# H-bridge_and_gate_drivers.net
KiCad netlist of a schematic drawn in Altium Designer
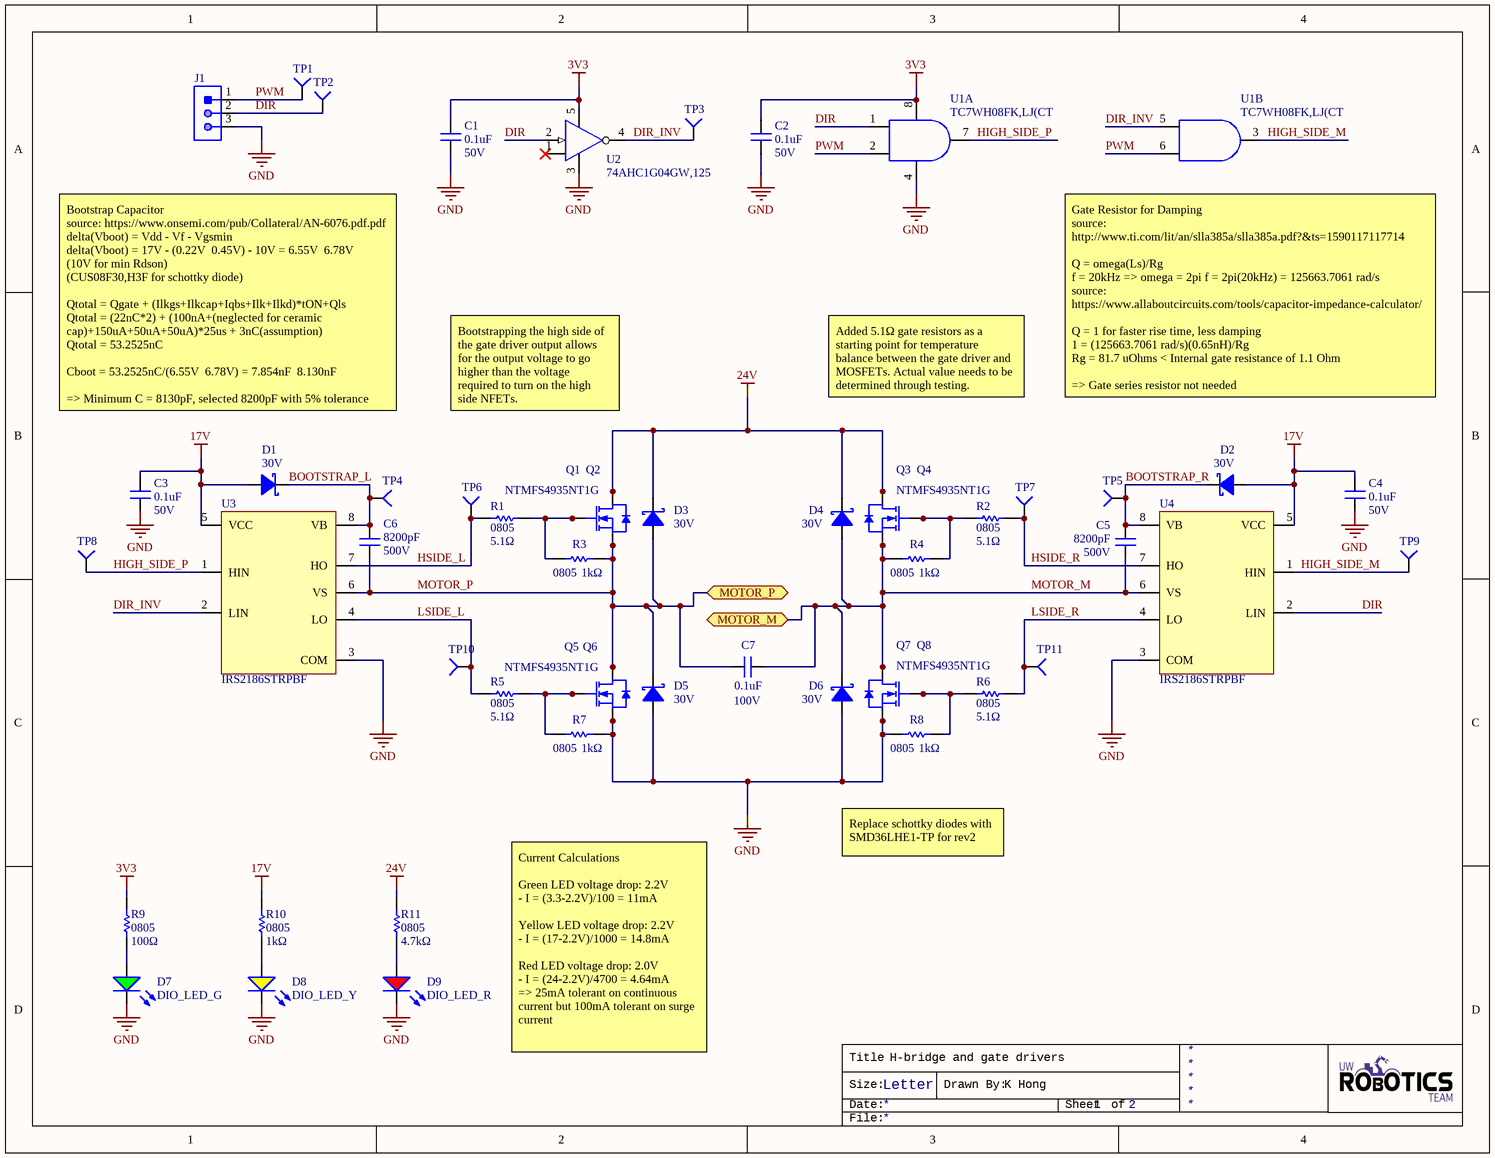
[diagram p0: H-bridge and gate drivers.SchDoc]

(export (version "E")
  (design (tool "Eeschema 10.0.6"))
  (components
    (comp (ref "C1")
      (value "0.1uF")
      (footprint "CAPC2012X140N")
      (description "CAP CER 0.1UF 50V X7R 0805")
      (fields
        (field (name "TOLERANCE") "10%")
        (field (name "VOLTAGE RATING") "50V")
        (field (name "Comment") "CAP_0.1uF_50V_0805")
      )
      (libsource (lib "UWRT_Schematic_Library_2020") (part "CAP_0.1uF_50V_0805"))
    )
    (comp (ref "C2")
      (value "0.1uF")
      (footprint "CAPC2012X140N")
      (description "CAP CER 0.1UF 50V X7R 0805")
      (fields
        (field (name "TOLERANCE") "10%")
        (field (name "VOLTAGE RATING") "50V")
        (field (name "Comment") "CAP_0.1uF_50V_0805")
      )
      (libsource (lib "UWRT_Schematic_Library_2020") (part "CAP_0.1uF_50V_0805"))
    )
    (comp (ref "C3")
      (value "0.1uF")
      (footprint "CAPC2012X140N")
      (description "CAP CER 0.1UF 50V X7R 0805")
      (fields
        (field (name "TOLERANCE") "10%")
        (field (name "VOLTAGE RATING") "50V")
        (field (name "Comment") "CAP_0.1uF_50V_0805")
      )
      (libsource (lib "UWRT_Schematic_Library_2020") (part "CAP_0.1uF_50V_0805"))
    )
    (comp (ref "C4")
      (value "0.1uF")
      (footprint "CAPC2012X140N")
      (description "CAP CER 0.1UF 50V X7R 0805")
      (fields
        (field (name "TOLERANCE") "10%")
        (field (name "VOLTAGE RATING") "50V")
        (field (name "Comment") "CAP_0.1uF_50V_0805")
      )
      (libsource (lib "UWRT_Schematic_Library_2020") (part "CAP_0.1uF_50V_0805"))
    )
    (comp (ref "C5")
      (value "CAP_8200pF_500V_1206")
      (footprint "CAPC1206(3216)")
      (description "Cap 0.0082uF 500Vdc C0G 5% SMD 1206 125°C Paper T/R")
      (fields
        (field (name "TOLERANCE") "5%")
        (field (name "CAPACITANCE") "8200pF")
        (field (name "VOLTAGE RATING (DC)") "500V")
      )
      (libsource (lib "UWRT_Schematic_Library_2020") (part "CAP_8200pF_500V_1206"))
    )
    (comp (ref "C6")
      (value "CAP_8200pF_500V_1206")
      (footprint "CAPC1206(3216)")
      (description "Cap 0.0082uF 500Vdc C0G 5% SMD 1206 125°C Paper T/R")
      (fields
        (field (name "TOLERANCE") "5%")
        (field (name "CAPACITANCE") "8200pF")
        (field (name "VOLTAGE RATING (DC)") "500V")
      )
      (libsource (lib "UWRT_Schematic_Library_2020") (part "CAP_8200pF_500V_1206"))
    )
    (comp (ref "C7")
      (value "CAP_0.1uF_100V_FILM")
      (footprint "MKS2D031001A00MSSD")
      (description "CAP FILM 0.1UF 100V RADIAL")
      (fields
        (field (name "CAPACITANCE") "0.1uF")
        (field (name "TOLERANCE") "20%")
        (field (name "VOLTAGE(DC)") "100V")
      )
      (libsource (lib "UWRT_Schematic_Library_2020") (part "CAP_0.1uF_100V_FILM"))
    )
    (comp (ref "D1")
      (value "DIO_SCHOTTKY_30V_800mA")
      (footprint "SOD-323_UNIDIR")
      (description "DIODE SCHOTTKY 30V 800MA USC")
      (fields (field (name "VR (MAX)") "30V"))
      (libsource (lib "UWRT_Schematic_Library_2020") (part "DIO_SCHOTTKY_30V_800mA"))
    )
    (comp (ref "D2")
      (value "DIO_SCHOTTKY_30V_800mA")
      (footprint "SOD-323_UNIDIR")
      (description "DIODE SCHOTTKY 30V 800MA USC")
      (fields (field (name "VR (MAX)") "30V"))
      (libsource (lib "UWRT_Schematic_Library_2020") (part "DIO_SCHOTTKY_30V_800mA"))
    )
    (comp (ref "D3")
      (value "DIO_SCHOTTKY_30V_800mA")
      (footprint "SOD-323_UNIDIR")
      (description "DIODE SCHOTTKY 30V 800MA USC")
      (fields (field (name "VR (MAX)") "30V"))
      (libsource (lib "UWRT_Schematic_Library_2020") (part "DIO_SCHOTTKY_30V_800mA"))
    )
    (comp (ref "D4")
      (value "DIO_SCHOTTKY_30V_800mA")
      (footprint "SOD-323_UNIDIR")
      (description "DIODE SCHOTTKY 30V 800MA USC")
      (fields (field (name "VR (MAX)") "30V"))
      (libsource (lib "UWRT_Schematic_Library_2020") (part "DIO_SCHOTTKY_30V_800mA"))
    )
    (comp (ref "D5")
      (value "DIO_SCHOTTKY_30V_800mA")
      (footprint "SOD-323_UNIDIR")
      (description "DIODE SCHOTTKY 30V 800MA USC")
      (fields (field (name "VR (MAX)") "30V"))
      (libsource (lib "UWRT_Schematic_Library_2020") (part "DIO_SCHOTTKY_30V_800mA"))
    )
    (comp (ref "D6")
      (value "DIO_SCHOTTKY_30V_800mA")
      (footprint "SOD-323_UNIDIR")
      (description "DIODE SCHOTTKY 30V 800MA USC")
      (fields (field (name "VR (MAX)") "30V"))
      (libsource (lib "UWRT_Schematic_Library_2020") (part "DIO_SCHOTTKY_30V_800mA"))
    )
    (comp (ref "D7")
      (value "DIO_LED_G")
      (footprint "LED_0805_LINE")
      (description "LED GREEN DIFFUSED 0805 SMD")
      (libsource (lib "UWRT_Schematic_Library_2020") (part "DIO_LED_G"))
    )
    (comp (ref "D8")
      (value "DIO_LED_Y")
      (footprint "LED_0805_LINE")
      (description "LED YELLOW DIFFUSED 0805 SMD")
      (libsource (lib "UWRT_Schematic_Library_2020") (part "DIO_LED_Y"))
    )
    (comp (ref "D9")
      (value "DIO_LED_R")
      (footprint "LED_0805_LINE")
      (description "LED RED DIFFUSED 0805 SMD")
      (libsource (lib "UWRT_Schematic_Library_2020") (part "DIO_LED_R"))
    )
    (comp (ref "J1")
      (value "CON_3M_TERM")
      (footprint "1935174")
      (description "TERM BLK 3POS SIDE ENTRY 5MM")
      (fields (field (name "VOLTAGE") "300V"))
      (libsource (lib "UWRT_Schematic_Library_2020") (part "CON_3M_TERM"))
    )
    (comp (ref "Q1")
      (value "NTMFS4935NT1G")
      (footprint "SO8-FL")
      (description "MOSFET N-CH 30V 13A SO8FL")
      (libsource (lib "UWRT_Schematic_Library_2020") (part "NTMFS4935NT1G"))
    )
    (comp (ref "Q2")
      (value "NTMFS4935NT1G")
      (footprint "SO8-FL")
      (description "MOSFET N-CH 30V 13A SO8FL")
      (fields (field (name "MANUFACTURER PART NUMBER 1") "NTMFS4935NT1G"))
      (libsource (lib "UWRT_Schematic_Library_2020") (part "NTMFS4935NT1G"))
    )
    (comp (ref "Q3")
      (value "NTMFS4935NT1G")
      (footprint "SO8-FL")
      (description "MOSFET N-CH 30V 13A SO8FL")
      (fields (field (name "MANUFACTURER PART NUMBER 1") "NTMFS4935NT1G"))
      (libsource (lib "UWRT_Schematic_Library_2020") (part "NTMFS4935NT1G"))
    )
    (comp (ref "Q4")
      (value "NTMFS4935NT1G")
      (footprint "SO8-FL")
      (description "MOSFET N-CH 30V 13A SO8FL")
      (libsource (lib "UWRT_Schematic_Library_2020") (part "NTMFS4935NT1G"))
    )
    (comp (ref "Q5")
      (value "NTMFS4935NT1G")
      (footprint "SO8-FL")
      (description "MOSFET N-CH 30V 13A SO8FL")
      (libsource (lib "UWRT_Schematic_Library_2020") (part "NTMFS4935NT1G"))
    )
    (comp (ref "Q6")
      (value "NTMFS4935NT1G")
      (footprint "SO8-FL")
      (description "MOSFET N-CH 30V 13A SO8FL")
      (fields (field (name "MANUFACTURER PART NUMBER 1") "NTMFS4935NT1G"))
      (libsource (lib "UWRT_Schematic_Library_2020") (part "NTMFS4935NT1G"))
    )
    (comp (ref "Q7")
      (value "NTMFS4935NT1G")
      (footprint "SO8-FL")
      (description "MOSFET N-CH 30V 13A SO8FL")
      (libsource (lib "UWRT_Schematic_Library_2020") (part "NTMFS4935NT1G"))
    )
    (comp (ref "Q8")
      (value "NTMFS4935NT1G")
      (footprint "SO8-FL")
      (description "MOSFET N-CH 30V 13A SO8FL")
      (fields (field (name "MANUFACTURER PART NUMBER 1") "NTMFS4935NT1G"))
      (libsource (lib "UWRT_Schematic_Library_2020") (part "NTMFS4935NT1G"))
    )
    (comp (ref "R1")
      (value "5.1Ω")
      (footprint "RESC2013X70X40LL20T20")
      (description "RES SMD 5.1 OHM 5% 1/8W 0805")
      (fields (field (name "CASE CODE (IMPERIAL)") "0805") (field (name "Comment") "RES_5.1Ω_0805"))
      (libsource (lib "UWRT_Schematic_Library_2020") (part "RES_5.1Ω_0805"))
    )
    (comp (ref "R2")
      (value "5.1Ω")
      (footprint "RESC2013X70X40LL20T20")
      (description "RES SMD 5.1 OHM 5% 1/8W 0805")
      (fields (field (name "CASE CODE (IMPERIAL)") "0805") (field (name "Comment") "RES_5.1Ω_0805"))
      (libsource (lib "UWRT_Schematic_Library_2020") (part "RES_5.1Ω_0805"))
    )
    (comp (ref "R3")
      (value "1kΩ")
      (footprint "RESC2012X60N")
      (description "RES SMD 1K OHM 1% 1/8W 0805")
      (fields
        (field (name "CASE CODE (IMPERIAL)") "0805")
        (field (name "TOLERANCE") "1%")
        (field (name "Comment") "RES_1kΩ_0805")
      )
      (libsource (lib "UWRT_Schematic_Library_2020") (part "RES_1kΩ_0805"))
    )
    (comp (ref "R4")
      (value "1kΩ")
      (footprint "RESC2012X60N")
      (description "RES SMD 1K OHM 1% 1/8W 0805")
      (fields
        (field (name "CASE CODE (IMPERIAL)") "0805")
        (field (name "TOLERANCE") "1%")
        (field (name "Comment") "RES_1kΩ_0805")
      )
      (libsource (lib "UWRT_Schematic_Library_2020") (part "RES_1kΩ_0805"))
    )
    (comp (ref "R5")
      (value "5.1Ω")
      (footprint "RESC2013X70X40LL20T20")
      (description "RES SMD 5.1 OHM 5% 1/8W 0805")
      (fields (field (name "CASE CODE (IMPERIAL)") "0805") (field (name "Comment") "RES_5.1Ω_0805"))
      (libsource (lib "UWRT_Schematic_Library_2020") (part "RES_5.1Ω_0805"))
    )
    (comp (ref "R6")
      (value "5.1Ω")
      (footprint "RESC2013X70X40LL20T20")
      (description "RES SMD 5.1 OHM 5% 1/8W 0805")
      (fields (field (name "CASE CODE (IMPERIAL)") "0805") (field (name "Comment") "RES_5.1Ω_0805"))
      (libsource (lib "UWRT_Schematic_Library_2020") (part "RES_5.1Ω_0805"))
    )
    (comp (ref "R7")
      (value "1kΩ")
      (footprint "RESC2012X60N")
      (description "RES SMD 1K OHM 1% 1/8W 0805")
      (fields
        (field (name "CASE CODE (IMPERIAL)") "0805")
        (field (name "TOLERANCE") "1%")
        (field (name "Comment") "RES_1kΩ_0805")
      )
      (libsource (lib "UWRT_Schematic_Library_2020") (part "RES_1kΩ_0805"))
    )
    (comp (ref "R8")
      (value "1kΩ")
      (footprint "RESC2012X60N")
      (description "RES SMD 1K OHM 1% 1/8W 0805")
      (fields
        (field (name "CASE CODE (IMPERIAL)") "0805")
        (field (name "TOLERANCE") "1%")
        (field (name "Comment") "RES_1kΩ_0805")
      )
      (libsource (lib "UWRT_Schematic_Library_2020") (part "RES_1kΩ_0805"))
    )
    (comp (ref "R9")
      (value "100Ω")
      (footprint "RESC2012X60N")
      (description "RES SMD 100 OHM 1% 1/8W 0805")
      (fields (field (name "CASE CODE (IMPERIAL)") "0805") (field (name "Comment") "RES_100Ω_0805"))
      (libsource (lib "UWRT_Schematic_Library_2020") (part "RES_100Ω_0805"))
    )
    (comp (ref "R10")
      (value "1kΩ")
      (footprint "RESC2012X60N")
      (description "RES SMD 1K OHM 1% 1/8W 0805")
      (fields
        (field (name "TOLERANCE") "1%")
        (field (name "CASE CODE (IMPERIAL)") "0805")
        (field (name "Comment") "RES_1kΩ_0805")
      )
      (libsource (lib "UWRT_Schematic_Library_2020") (part "RES_1kΩ_0805"))
    )
    (comp (ref "R11")
      (value "4.7kΩ")
      (footprint "RESC2012X60N")
      (description "RES SMD 4.7K OHM 5% 1/8W 0805")
      (fields
        (field (name "TOLERANCE") "5%")
        (field (name "CASE CODE (IMPERIAL)") "0805")
        (field (name "Comment") "RES_4.7kΩ_0805")
      )
      (libsource (lib "UWRT_Schematic_Library_2020") (part "RES_4.7kΩ_0805"))
    )
    (comp (ref "TP1")
      (value "TESTPOINT_SMD")
      (footprint "TESTPOINT")
      (libsource (lib "UWRT_Schematic_Library_2020") (part "TESTPOINT_SMD"))
    )
    (comp (ref "TP2")
      (value "TESTPOINT_SMD")
      (footprint "TESTPOINT")
      (libsource (lib "UWRT_Schematic_Library_2020") (part "TESTPOINT_SMD"))
    )
    (comp (ref "TP3")
      (value "TESTPOINT_SMD")
      (footprint "TESTPOINT")
      (libsource (lib "UWRT_Schematic_Library_2020") (part "TESTPOINT_SMD"))
    )
    (comp (ref "TP4")
      (value "TESTPOINT_SMD")
      (footprint "TESTPOINT")
      (libsource (lib "UWRT_Schematic_Library_2020") (part "TESTPOINT_SMD"))
    )
    (comp (ref "TP5")
      (value "TESTPOINT_SMD")
      (footprint "TESTPOINT")
      (libsource (lib "UWRT_Schematic_Library_2020") (part "TESTPOINT_SMD"))
    )
    (comp (ref "TP6")
      (value "TESTPOINT_SMD")
      (footprint "TESTPOINT")
      (libsource (lib "UWRT_Schematic_Library_2020") (part "TESTPOINT_SMD"))
    )
    (comp (ref "TP7")
      (value "TESTPOINT_SMD")
      (footprint "TESTPOINT")
      (libsource (lib "UWRT_Schematic_Library_2020") (part "TESTPOINT_SMD"))
    )
    (comp (ref "TP8")
      (value "TESTPOINT_SMD")
      (footprint "TESTPOINT")
      (libsource (lib "UWRT_Schematic_Library_2020") (part "TESTPOINT_SMD"))
    )
    (comp (ref "TP9")
      (value "TESTPOINT_SMD")
      (footprint "TESTPOINT")
      (libsource (lib "UWRT_Schematic_Library_2020") (part "TESTPOINT_SMD"))
    )
    (comp (ref "TP10")
      (value "TESTPOINT_SMD")
      (footprint "TESTPOINT")
      (libsource (lib "UWRT_Schematic_Library_2020") (part "TESTPOINT_SMD"))
    )
    (comp (ref "TP11")
      (value "TESTPOINT_SMD")
      (footprint "TESTPOINT")
      (libsource (lib "UWRT_Schematic_Library_2020") (part "TESTPOINT_SMD"))
    )
    (comp (ref "U1")
      (value "TC7WH08FK,LJ(CT")
      (footprint "8-VFSOP")
      (description "AND Gate 2-Element 2-IN CMOS Automotive 8-Pin SSOP T/R")
      (fields (field (name "MANUFACTURER PART NUMBER 1") "TC7WH08FK,LJ(CT"))
      (libsource (lib "UWRT_Schematic_Library_2020") (part "TC7WH08FK,LJ(CT"))
    )
    (comp (ref "U2")
      (value "74AHC1G04GW,125")
      (footprint "SOT353")
      (description "74AHC Series 5 V High Speed Si-Gate CMOS Inverter Buffer Surface Mount - TSSOP-5")
      (fields (field (name "MANUFACTURER PART NUMBER 1") "74AHC1G04GW,125"))
      (libsource (lib "UWRT_Schematic_Library_2020") (part "74AHC1G04GW,125"))
    )
    (comp (ref "U3")
      (value "IRS2186STRPBF")
      (footprint "8-SOIC_M")
      (description "IC DRIVER HI/LO SIDE 600V 8-SOIC")
      (fields (field (name "MANUFACTURER PART NUMBER 1") "IRS2186STRPBF"))
      (libsource (lib "") (part "IRS2186STRPBF_1"))
    )
    (comp (ref "U4")
      (value "IRS2186STRPBF")
      (footprint "8-SOIC_M")
      (description "IC DRIVER HI/LO SIDE 600V 8-SOIC")
      (fields (field (name "MANUFACTURER PART NUMBER 1") "IRS2186STRPBF"))
      (libsource (lib "UWRT_Schematic_Library_2020") (part "IRS2186STRPBF"))
    )
  )
  (nets
    (net (code "1") (name "/BOOTSTRAP_L") (class "Default")
      (node (ref "C6") (pin "2") (pinfunction "2_2") (pintype "passive"))
      (node (ref "D1") (pin "2") (pinfunction "Cathode_2") (pintype "passive"))
      (node (ref "TP4") (pin "1") (pinfunction "=value_1") (pintype "passive"))
      (node (ref "U3") (pin "8") (pinfunction "VB_8") (pintype "passive"))
    )
    (net (code "2") (name "/BOOTSTRAP_R") (class "Default")
      (node (ref "C5") (pin "2") (pinfunction "2_2") (pintype "passive"))
      (node (ref "D2") (pin "2") (pinfunction "Cathode_2") (pintype "passive"))
      (node (ref "TP5") (pin "1") (pinfunction "=value_1") (pintype "passive"))
      (node (ref "U4") (pin "8") (pinfunction "VB_8") (pintype "passive"))
    )
    (net (code "3") (name "/DIR") (class "Default")
      (node (ref "J1") (pin "2") (pinfunction "2_2") (pintype "passive"))
      (node (ref "TP2") (pin "1") (pinfunction "=value_1") (pintype "passive"))
      (node (ref "U1") (pin "1") (pinfunction "A1_1") (pintype "passive"))
      (node (ref "U2") (pin "2") (pinfunction "A_2") (pintype "input"))
      (node (ref "U4") (pin "2") (pinfunction "LIN_2") (pintype "passive"))
    )
    (net (code "4") (name "/DIR_INV") (class "Default")
      (node (ref "TP3") (pin "1") (pinfunction "=value_1") (pintype "passive"))
      (node (ref "U1") (pin "5") (pinfunction "A2_5") (pintype "passive"))
      (node (ref "U2") (pin "4") (pinfunction "Y_4") (pintype "passive"))
      (node (ref "U3") (pin "2") (pinfunction "LIN_2") (pintype "passive"))
    )
    (net (code "5") (name "/HIGH_SIDE_M") (class "Default")
      (node (ref "TP9") (pin "1") (pinfunction "=value_1") (pintype "passive"))
      (node (ref "U1") (pin "3") (pinfunction "Y2_3") (pintype "passive"))
      (node (ref "U4") (pin "1") (pinfunction "HIN_1") (pintype "passive"))
    )
    (net (code "6") (name "/HIGH_SIDE_P") (class "Default")
      (node (ref "TP8") (pin "1") (pinfunction "=value_1") (pintype "passive"))
      (node (ref "U1") (pin "7") (pinfunction "Y1_7") (pintype "passive"))
      (node (ref "U3") (pin "1") (pinfunction "HIN_1") (pintype "passive"))
    )
    (net (code "7") (name "/HSIDE_L") (class "Default")
      (node (ref "R1") (pin "1") (pinfunction "1_1") (pintype "passive"))
      (node (ref "TP6") (pin "1") (pinfunction "=value_1") (pintype "passive"))
      (node (ref "U3") (pin "7") (pinfunction "HO_7") (pintype "passive"))
    )
    (net (code "8") (name "/HSIDE_R") (class "Default")
      (node (ref "R2") (pin "2") (pinfunction "2_2") (pintype "passive"))
      (node (ref "TP7") (pin "1") (pinfunction "=value_1") (pintype "passive"))
      (node (ref "U4") (pin "7") (pinfunction "HO_7") (pintype "passive"))
    )
    (net (code "9") (name "/LSIDE_L") (class "Default")
      (node (ref "R5") (pin "1") (pinfunction "1_1") (pintype "passive"))
      (node (ref "TP10") (pin "1") (pinfunction "=value_1") (pintype "passive"))
      (node (ref "U3") (pin "4") (pinfunction "LO_4") (pintype "passive"))
    )
    (net (code "10") (name "/LSIDE_R") (class "Default")
      (node (ref "R6") (pin "2") (pinfunction "2_2") (pintype "passive"))
      (node (ref "TP11") (pin "1") (pinfunction "=value_1") (pintype "passive"))
      (node (ref "U4") (pin "4") (pinfunction "LO_4") (pintype "passive"))
    )
    (net (code "11") (name "/MOTOR_M") (class "Default")
      (node (ref "C5") (pin "1") (pinfunction "1_1") (pintype "passive"))
      (node (ref "C7") (pin "2") (pinfunction "2_2") (pintype "passive"))
      (node (ref "D4") (pin "1") (pinfunction "Anode_1") (pintype "passive"))
      (node (ref "D6") (pin "2") (pinfunction "Cathode_2") (pintype "passive"))
      (node (ref "Q3") (pin "1") (pinfunction "Source_1") (pintype "passive"))
      (node (ref "Q4") (pin "1") (pinfunction "Source_1") (pintype "passive"))
      (node (ref "Q7") (pin "3") (pinfunction "Drain_3") (pintype "passive"))
      (node (ref "Q8") (pin "3") (pinfunction "Drain_3") (pintype "passive"))
      (node (ref "R4") (pin "1") (pinfunction "1_1") (pintype "passive"))
      (node (ref "U4") (pin "6") (pinfunction "VS_6") (pintype "passive"))
    )
    (net (code "12") (name "/MOTOR_P") (class "Default")
      (node (ref "C6") (pin "1") (pinfunction "1_1") (pintype "passive"))
      (node (ref "C7") (pin "1") (pinfunction "1_1") (pintype "passive"))
      (node (ref "D3") (pin "1") (pinfunction "Anode_1") (pintype "passive"))
      (node (ref "D5") (pin "2") (pinfunction "Cathode_2") (pintype "passive"))
      (node (ref "Q1") (pin "1") (pinfunction "Source_1") (pintype "passive"))
      (node (ref "Q2") (pin "1") (pinfunction "Source_1") (pintype "passive"))
      (node (ref "Q5") (pin "3") (pinfunction "Drain_3") (pintype "passive"))
      (node (ref "Q6") (pin "3") (pinfunction "Drain_3") (pintype "passive"))
      (node (ref "R3") (pin "2") (pinfunction "2_2") (pintype "passive"))
      (node (ref "U3") (pin "6") (pinfunction "VS_6") (pintype "passive"))
    )
    (net (code "13") (name "/PWM") (class "Default")
      (node (ref "J1") (pin "1") (pinfunction "1_1") (pintype "passive"))
      (node (ref "TP1") (pin "1") (pinfunction "=value_1") (pintype "passive"))
      (node (ref "U1") (pin "2") (pinfunction "B1_2") (pintype "passive"))
      (node (ref "U1") (pin "6") (pinfunction "B2_6") (pintype "passive"))
    )
    (net (code "14") (name "3V3") (class "Default")
      (node (ref "C1") (pin "2") (pinfunction "2_2") (pintype "passive"))
      (node (ref "C2") (pin "2") (pinfunction "2_2") (pintype "passive"))
      (node (ref "R9") (pin "2") (pinfunction "2_2") (pintype "passive"))
      (node (ref "U1") (pin "8") (pinfunction "Vcc_8") (pintype "passive"))
      (node (ref "U2") (pin "5") (pinfunction "Vcc_5") (pintype "passive"))
    )
    (net (code "15") (name "17V") (class "Default")
      (node (ref "C3") (pin "2") (pinfunction "2_2") (pintype "passive"))
      (node (ref "C4") (pin "2") (pinfunction "2_2") (pintype "passive"))
      (node (ref "D1") (pin "1") (pinfunction "Anode_1") (pintype "passive"))
      (node (ref "D2") (pin "1") (pinfunction "Anode_1") (pintype "passive"))
      (node (ref "R10") (pin "2") (pinfunction "2_2") (pintype "passive"))
      (node (ref "U3") (pin "5") (pinfunction "VCC_5") (pintype "passive"))
      (node (ref "U4") (pin "5") (pinfunction "VCC_5") (pintype "passive"))
    )
    (net (code "16") (name "24V") (class "Default")
      (node (ref "D3") (pin "2") (pinfunction "Cathode_2") (pintype "passive"))
      (node (ref "D4") (pin "2") (pinfunction "Cathode_2") (pintype "passive"))
      (node (ref "Q1") (pin "3") (pinfunction "Drain_3") (pintype "passive"))
      (node (ref "Q2") (pin "3") (pinfunction "Drain_3") (pintype "passive"))
      (node (ref "Q3") (pin "3") (pinfunction "Drain_3") (pintype "passive"))
      (node (ref "Q4") (pin "3") (pinfunction "Drain_3") (pintype "passive"))
      (node (ref "R11") (pin "2") (pinfunction "2_2") (pintype "passive"))
    )
    (net (code "17") (name "GND") (class "Default")
      (node (ref "C1") (pin "1") (pinfunction "1_1") (pintype "passive"))
      (node (ref "C2") (pin "1") (pinfunction "1_1") (pintype "passive"))
      (node (ref "C3") (pin "1") (pinfunction "1_1") (pintype "passive"))
      (node (ref "C4") (pin "1") (pinfunction "1_1") (pintype "passive"))
      (node (ref "D5") (pin "1") (pinfunction "Anode_1") (pintype "passive"))
      (node (ref "D6") (pin "1") (pinfunction "Anode_1") (pintype "passive"))
      (node (ref "D7") (pin "2") (pinfunction "K_2") (pintype "passive"))
      (node (ref "D8") (pin "2") (pinfunction "K_2") (pintype "passive"))
      (node (ref "D9") (pin "2") (pinfunction "K_2") (pintype "passive"))
      (node (ref "J1") (pin "3") (pinfunction "3_3") (pintype "passive"))
      (node (ref "Q5") (pin "1") (pinfunction "Source_1") (pintype "passive"))
      (node (ref "Q6") (pin "1") (pinfunction "Source_1") (pintype "passive"))
      (node (ref "Q7") (pin "1") (pinfunction "Source_1") (pintype "passive"))
      (node (ref "Q8") (pin "1") (pinfunction "Source_1") (pintype "passive"))
      (node (ref "R7") (pin "2") (pinfunction "2_2") (pintype "passive"))
      (node (ref "R8") (pin "1") (pinfunction "1_1") (pintype "passive"))
      (node (ref "U1") (pin "4") (pinfunction "GND_4") (pintype "passive"))
      (node (ref "U2") (pin "3") (pinfunction "GND_3") (pintype "passive"))
      (node (ref "U3") (pin "3") (pinfunction "COM_3") (pintype "passive"))
      (node (ref "U4") (pin "3") (pinfunction "COM_3") (pintype "passive"))
    )
    (net (code "18") (name "Net-(D7-A)") (class "Default")
      (node (ref "D7") (pin "1") (pinfunction "A_1") (pintype "passive"))
      (node (ref "R9") (pin "1") (pinfunction "1_1") (pintype "passive"))
    )
    (net (code "19") (name "Net-(D8-A)") (class "Default")
      (node (ref "D8") (pin "1") (pinfunction "A_1") (pintype "passive"))
      (node (ref "R10") (pin "1") (pinfunction "1_1") (pintype "passive"))
    )
    (net (code "20") (name "Net-(D9-A)") (class "Default")
      (node (ref "D9") (pin "1") (pinfunction "A_1") (pintype "passive"))
      (node (ref "R11") (pin "1") (pinfunction "1_1") (pintype "passive"))
    )
    (net (code "21") (name "Net-(Q1-Gate)") (class "Default")
      (node (ref "Q1") (pin "2") (pinfunction "Gate_2") (pintype "passive"))
      (node (ref "Q2") (pin "2") (pinfunction "Gate_2") (pintype "passive"))
      (node (ref "R1") (pin "2") (pinfunction "2_2") (pintype "passive"))
      (node (ref "R3") (pin "1") (pinfunction "1_1") (pintype "passive"))
    )
    (net (code "22") (name "Net-(Q3-Gate)") (class "Default")
      (node (ref "Q3") (pin "2") (pinfunction "Gate_2") (pintype "passive"))
      (node (ref "Q4") (pin "2") (pinfunction "Gate_2") (pintype "passive"))
      (node (ref "R2") (pin "1") (pinfunction "1_1") (pintype "passive"))
      (node (ref "R4") (pin "2") (pinfunction "2_2") (pintype "passive"))
    )
    (net (code "23") (name "Net-(Q5-Gate)") (class "Default")
      (node (ref "Q5") (pin "2") (pinfunction "Gate_2") (pintype "passive"))
      (node (ref "Q6") (pin "2") (pinfunction "Gate_2") (pintype "passive"))
      (node (ref "R5") (pin "2") (pinfunction "2_2") (pintype "passive"))
      (node (ref "R7") (pin "1") (pinfunction "1_1") (pintype "passive"))
    )
    (net (code "24") (name "Net-(Q7-Gate)") (class "Default")
      (node (ref "Q7") (pin "2") (pinfunction "Gate_2") (pintype "passive"))
      (node (ref "Q8") (pin "2") (pinfunction "Gate_2") (pintype "passive"))
      (node (ref "R6") (pin "1") (pinfunction "1_1") (pintype "passive"))
      (node (ref "R8") (pin "2") (pinfunction "2_2") (pintype "passive"))
    )
    (net (code "25") (name "unconnected-(U2-NC-Pad1)") (class "Default")
      (node (ref "U2") (pin "1") (pinfunction "NC_1") (pintype "tri_state+no_connect"))
    )
  )
)
